# 10_FPGA_misc.net
KiCad netlist of a schematic drawn in Altium Designer
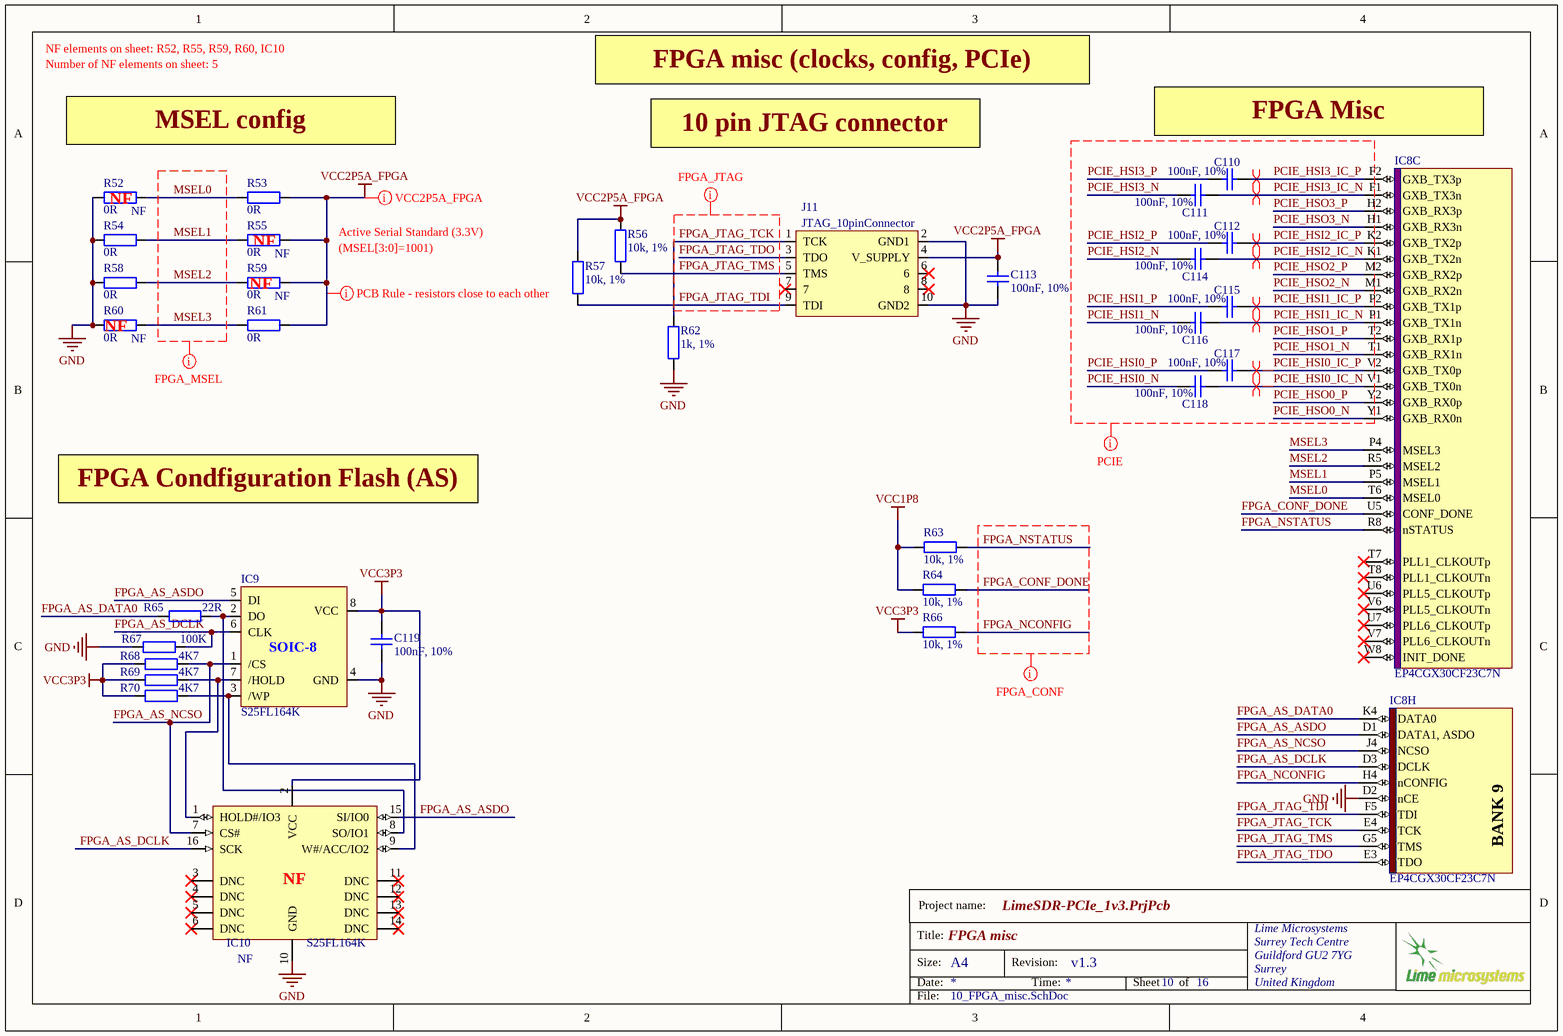
[diagram p0: 10_FPGA_misc.SchDoc]

(export (version "E")
  (design (tool "Eeschema 10.0.6"))
  (components
    (comp (ref "C110")
      (value "100nF, 10%")
      (footprint "CAP0402")
      (fields
        (field (name "TOLERANCE") "10 %")
        (field (name "MANUFACTURER") "Murata Electronics")
        (field (name "MANUFACTURER PART NUMBER") "GRM155R71C104KA88D")
      )
      (libsource (lib "LimeFPGAboard_schLib") (part "Cap_0603"))
    )
    (comp (ref "C111")
      (value "100nF, 10%")
      (footprint "CAP0402")
      (fields
        (field (name "TOLERANCE") "10 %")
        (field (name "MANUFACTURER") "Murata Electronics")
        (field (name "MANUFACTURER PART NUMBER") "GRM155R71C104KA88D")
      )
      (libsource (lib "LimeFPGAboard_schLib") (part "Cap_0603"))
    )
    (comp (ref "C112")
      (value "100nF, 10%")
      (footprint "CAP0402")
      (fields
        (field (name "TOLERANCE") "10 %")
        (field (name "MANUFACTURER") "Murata Electronics")
        (field (name "MANUFACTURER PART NUMBER") "GRM155R71C104KA88D")
      )
      (libsource (lib "LimeFPGAboard_schLib") (part "Cap_0603"))
    )
    (comp (ref "C113")
      (value "100nF, 10%")
      (footprint "CAP0402")
      (fields
        (field (name "TOLERANCE") "10 %")
        (field (name "MANUFACTURER") "Murata Electronics")
        (field (name "MANUFACTURER PART NUMBER") "GRM155R71C104KA88D")
      )
      (libsource (lib "LimeFPGAboard_schLib") (part "Cap_0603"))
    )
    (comp (ref "C114")
      (value "100nF, 10%")
      (footprint "CAP0402")
      (fields
        (field (name "TOLERANCE") "10 %")
        (field (name "MANUFACTURER") "Murata Electronics")
        (field (name "MANUFACTURER PART NUMBER") "GRM155R71C104KA88D")
      )
      (libsource (lib "LimeFPGAboard_schLib") (part "Cap_0603"))
    )
    (comp (ref "C115")
      (value "100nF, 10%")
      (footprint "CAP0402")
      (fields
        (field (name "TOLERANCE") "10 %")
        (field (name "MANUFACTURER") "Murata Electronics")
        (field (name "MANUFACTURER PART NUMBER") "GRM155R71C104KA88D")
      )
      (libsource (lib "LimeFPGAboard_schLib") (part "Cap_0603"))
    )
    (comp (ref "C116")
      (value "100nF, 10%")
      (footprint "CAP0402")
      (fields
        (field (name "TOLERANCE") "10 %")
        (field (name "MANUFACTURER") "Murata Electronics")
        (field (name "MANUFACTURER PART NUMBER") "GRM155R71C104KA88D")
      )
      (libsource (lib "LimeFPGAboard_schLib") (part "Cap_0603"))
    )
    (comp (ref "C117")
      (value "100nF, 10%")
      (footprint "CAP0402")
      (fields
        (field (name "TOLERANCE") "10 %")
        (field (name "MANUFACTURER") "Murata Electronics")
        (field (name "MANUFACTURER PART NUMBER") "GRM155R71C104KA88D")
      )
      (libsource (lib "LimeFPGAboard_schLib") (part "Cap_0603"))
    )
    (comp (ref "C118")
      (value "100nF, 10%")
      (footprint "CAP0402")
      (fields
        (field (name "TOLERANCE") "10 %")
        (field (name "MANUFACTURER") "Murata Electronics")
        (field (name "MANUFACTURER PART NUMBER") "GRM155R71C104KA88D")
      )
      (libsource (lib "LimeFPGAboard_schLib") (part "Cap_0603"))
    )
    (comp (ref "C119")
      (value "100nF, 10%")
      (footprint "CAP0402")
      (fields
        (field (name "TOLERANCE") "10 %")
        (field (name "MANUFACTURER") "Murata Electronics")
        (field (name "MANUFACTURER PART NUMBER") "GRM155R71C104KA88D")
      )
      (libsource (lib "LimeFPGAboard_schLib") (part "Cap_0603"))
    )
    (comp (ref "IC8")
      (value "EP4CGX30CF23C7N")
      (footprint "ALTR-FBGA484_A-200")
      (fields (field (name "MANUFACTURER") "Altera"))
      (libsource (lib "LimeMicroAltiumLib_schLib") (part "EP4CGX30CF23C7N"))
    )
    (comp (ref "IC9")
      (value "S25FL164K")
      (footprint "S25FL164K_WSO8N")
      (fields (field (name "MANUFACTURER") "Cypress Semiconductor Corp"))
      (libsource (lib "LimeMicroAltiumLib_schLib") (part "W25Q32FV"))
    )
    (comp (ref "IC10")
      (value "S25FL164K")
      (footprint "SOIC16_WIDE")
      (fields (field (name "ASSEMBLY INFO") "NF") (field (name "MANUFACTURER") "Cypress Semiconductor Corp"))
      (libsource (lib "LimeMicroAltiumLib_schLib") (part "S25FL032P"))
    )
    (comp (ref "J11")
      (value "JTAG_10pinConnector")
      (footprint "HEADER5x2_SM")
      (fields (field (name "MANUFACTURER") "MOLEX"))
      (libsource (lib "LimeFPGAboard_schLib") (part "JTAG_connector_10pin"))
    )
    (comp (ref "R52")
      (value "0R")
      (footprint "RES0402")
      (fields (field (name "MANUFACTURER") "Yageo") (field (name "ASSEMBLY INFO") "NF"))
      (libsource (lib "LimeFPGAboard_schLib") (part "Res_0402"))
    )
    (comp (ref "R53")
      (value "0R")
      (footprint "RES0402")
      (fields (field (name "MANUFACTURER") "Yageo"))
      (libsource (lib "LimeFPGAboard_schLib") (part "Res_0402"))
    )
    (comp (ref "R54")
      (value "0R")
      (footprint "RES0402")
      (fields (field (name "MANUFACTURER") "Yageo"))
      (libsource (lib "LimeFPGAboard_schLib") (part "Res_0402"))
    )
    (comp (ref "R55")
      (value "0R")
      (footprint "RES0402")
      (fields (field (name "MANUFACTURER") "Yageo") (field (name "ASSEMBLY INFO") "NF"))
      (libsource (lib "LimeFPGAboard_schLib") (part "Res_0402"))
    )
    (comp (ref "R56")
      (value "10k, 1%")
      (footprint "RES0402")
      (fields (field (name "MANUFACTURER") "Yageo") (field (name "TOLERANCE") "±1%"))
      (libsource (lib "LimeMicroAltiumLib_schLib") (part "Res_0402"))
    )
    (comp (ref "R57")
      (value "10k, 1%")
      (footprint "RES0402")
      (fields (field (name "MANUFACTURER") "Yageo") (field (name "TOLERANCE") "±1%"))
      (libsource (lib "LimeMicroAltiumLib_schLib") (part "Res_0402"))
    )
    (comp (ref "R58")
      (value "0R")
      (footprint "RES0402")
      (fields (field (name "MANUFACTURER") "Yageo"))
      (libsource (lib "LimeFPGAboard_schLib") (part "Res_0402"))
    )
    (comp (ref "R59")
      (value "0R")
      (footprint "RES0402")
      (fields (field (name "MANUFACTURER") "Yageo") (field (name "ASSEMBLY INFO") "NF"))
      (libsource (lib "LimeFPGAboard_schLib") (part "Res_0402"))
    )
    (comp (ref "R60")
      (value "0R")
      (footprint "RES0402")
      (fields (field (name "MANUFACTURER") "Yageo") (field (name "ASSEMBLY INFO") "NF"))
      (libsource (lib "LimeFPGAboard_schLib") (part "Res_0402"))
    )
    (comp (ref "R61")
      (value "0R")
      (footprint "RES0402")
      (fields (field (name "MANUFACTURER") "Yageo"))
      (libsource (lib "LimeFPGAboard_schLib") (part "Res_0402"))
    )
    (comp (ref "R62")
      (value "1k, 1%")
      (footprint "RES0402")
      (fields (field (name "MANUFACTURER") "Stackpole Electronics Inc") (field (name "TOLERANCE") "±1%"))
      (libsource (lib "LimeMicroAltiumLib_schLib") (part "Res_0402"))
    )
    (comp (ref "R63")
      (value "10k, 1%")
      (footprint "RES0402")
      (fields (field (name "MANUFACTURER") "Yageo") (field (name "TOLERANCE") "±1%"))
      (libsource (lib "LimeMicroAltiumLib_schLib") (part "Res_0402"))
    )
    (comp (ref "R64")
      (value "10k, 1%")
      (footprint "RES0402")
      (fields (field (name "MANUFACTURER") "Yageo") (field (name "TOLERANCE") "±1%"))
      (libsource (lib "LimeMicroAltiumLib_schLib") (part "Res_0402"))
    )
    (comp (ref "R65")
      (value "22R")
      (footprint "RES0402")
      (fields (field (name "TOLERANCE") "±1%") (field (name "MANUFACTURER") "Yageo"))
      (libsource (lib "LimeFPGAboard_schLib") (part "Res_0402"))
    )
    (comp (ref "R66")
      (value "10k, 1%")
      (footprint "RES0402")
      (fields (field (name "MANUFACTURER") "Yageo") (field (name "TOLERANCE") "±1%"))
      (libsource (lib "LimeMicroAltiumLib_schLib") (part "Res_0402"))
    )
    (comp (ref "R67")
      (value "100K")
      (footprint "RES0402")
      (fields
        (field (name "TOLERANCE") "±5%")
        (field (name "MANUFACTURER") "Panasonic Electronic Components")
      )
      (libsource (lib "LimeFPGAboard_schLib") (part "Res_0402"))
    )
    (comp (ref "R68")
      (value "4K7")
      (footprint "RES0402")
      (fields (field (name "TOLERANCE") "±5%") (field (name "MANUFACTURER") "Stackpole Electronics Inc."))
      (libsource (lib "LimeFPGAboard_schLib") (part "Res_0402"))
    )
    (comp (ref "R69")
      (value "4K7")
      (footprint "RES0402")
      (fields (field (name "TOLERANCE") "±5%") (field (name "MANUFACTURER") "Stackpole Electronics Inc."))
      (libsource (lib "LimeFPGAboard_schLib") (part "Res_0402"))
    )
    (comp (ref "R70")
      (value "4K7")
      (footprint "RES0402")
      (fields (field (name "TOLERANCE") "±5%") (field (name "MANUFACTURER") "Stackpole Electronics Inc."))
      (libsource (lib "LimeFPGAboard_schLib") (part "Res_0402"))
    )
  )
  (nets
    (net (code "1") (name "/FPGA_AS_ASDO") (class "Default")
      (node (ref "IC10") (pin "15") (pinfunction "SI/IO0_15") (pintype "bidirectional"))
      (node (ref "IC8") (pin "D1") (pinfunction "DATA1,_ASDO_D1") (pintype "bidirectional"))
      (node (ref "IC9") (pin "5") (pinfunction "DI_5") (pintype "passive"))
    )
    (net (code "2") (name "/FPGA_AS_DATA0") (class "Default")
      (node (ref "IC8") (pin "K4") (pinfunction "DATA0_K4") (pintype "bidirectional"))
      (node (ref "R65") (pin "2") (pinfunction "2_2") (pintype "passive"))
    )
    (net (code "3") (name "/FPGA_AS_DCLK") (class "Default")
      (node (ref "IC10") (pin "16") (pinfunction "SCK_16") (pintype "input"))
      (node (ref "IC8") (pin "D3") (pinfunction "DCLK_D3") (pintype "bidirectional"))
      (node (ref "IC9") (pin "6") (pinfunction "CLK_6") (pintype "passive"))
      (node (ref "R67") (pin "1") (pinfunction "1_1") (pintype "passive"))
    )
    (net (code "4") (name "/FPGA_AS_NCSO") (class "Default")
      (node (ref "IC10") (pin "7") (pinfunction "CS#_7") (pintype "input"))
      (node (ref "IC8") (pin "J4") (pinfunction "NCSO_J4") (pintype "bidirectional"))
      (node (ref "IC9") (pin "1") (pinfunction "/CS_1") (pintype "passive"))
      (node (ref "R68") (pin "2") (pinfunction "2_2") (pintype "passive"))
    )
    (net (code "5") (name "/FPGA_CONF_DONE") (class "Default")
      (node (ref "IC8") (pin "U5") (pinfunction "CONF_DONE_U5") (pintype "bidirectional"))
      (node (ref "R64") (pin "2") (pinfunction "2_2") (pintype "passive"))
    )
    (net (code "6") (name "/FPGA_JTAG_TCK") (class "Default")
      (node (ref "IC8") (pin "E4") (pinfunction "TCK_E4") (pintype "bidirectional"))
      (node (ref "J11") (pin "1") (pinfunction "TCK_1") (pintype "passive"))
      (node (ref "R62") (pin "1") (pinfunction "1_1") (pintype "passive"))
    )
    (net (code "7") (name "/FPGA_JTAG_TDI") (class "Default")
      (node (ref "IC8") (pin "F5") (pinfunction "TDI_F5") (pintype "bidirectional"))
      (node (ref "J11") (pin "9") (pinfunction "TDI_9") (pintype "passive"))
      (node (ref "R57") (pin "2") (pinfunction "2_2") (pintype "passive"))
    )
    (net (code "8") (name "/FPGA_JTAG_TDO") (class "Default")
      (node (ref "IC8") (pin "E3") (pinfunction "TDO_E3") (pintype "bidirectional"))
      (node (ref "J11") (pin "3") (pinfunction "TDO_3") (pintype "passive"))
    )
    (net (code "9") (name "/FPGA_JTAG_TMS") (class "Default")
      (node (ref "IC8") (pin "G5") (pinfunction "TMS_G5") (pintype "bidirectional"))
      (node (ref "J11") (pin "5") (pinfunction "TMS_5") (pintype "passive"))
      (node (ref "R56") (pin "2") (pinfunction "2_2") (pintype "passive"))
    )
    (net (code "10") (name "/FPGA_NCONFIG") (class "Default")
      (node (ref "IC8") (pin "H4") (pinfunction "nCONFIG_H4") (pintype "bidirectional"))
      (node (ref "R66") (pin "2") (pinfunction "2_2") (pintype "passive"))
    )
    (net (code "11") (name "/FPGA_NSTATUS") (class "Default")
      (node (ref "IC8") (pin "R8") (pinfunction "nSTATUS_R8") (pintype "bidirectional"))
      (node (ref "R63") (pin "2") (pinfunction "2_2") (pintype "passive"))
    )
    (net (code "12") (name "/MSEL0") (class "Default")
      (node (ref "IC8") (pin "T6") (pinfunction "MSEL0_T6") (pintype "bidirectional"))
      (node (ref "R52") (pin "1") (pinfunction "1_1") (pintype "passive"))
      (node (ref "R53") (pin "2") (pinfunction "2_2") (pintype "passive"))
    )
    (net (code "13") (name "/MSEL1") (class "Default")
      (node (ref "IC8") (pin "P5") (pinfunction "MSEL1_P5") (pintype "bidirectional"))
      (node (ref "R54") (pin "1") (pinfunction "1_1") (pintype "passive"))
      (node (ref "R55") (pin "2") (pinfunction "2_2") (pintype "passive"))
    )
    (net (code "14") (name "/MSEL2") (class "Default")
      (node (ref "IC8") (pin "R5") (pinfunction "MSEL2_R5") (pintype "bidirectional"))
      (node (ref "R58") (pin "1") (pinfunction "1_1") (pintype "passive"))
      (node (ref "R59") (pin "2") (pinfunction "2_2") (pintype "passive"))
    )
    (net (code "15") (name "/MSEL3") (class "Default")
      (node (ref "IC8") (pin "P4") (pinfunction "MSEL3_P4") (pintype "bidirectional"))
      (node (ref "R60") (pin "1") (pinfunction "1_1") (pintype "passive"))
      (node (ref "R61") (pin "2") (pinfunction "2_2") (pintype "passive"))
    )
    (net (code "16") (name "/PCIE_HSI0_IC_N") (class "Default")
      (node (ref "C118") (pin "1") (pinfunction "1_1") (pintype "passive"))
      (node (ref "IC8") (pin "V1") (pinfunction "GXB_TX0n_V1") (pintype "bidirectional"))
    )
    (net (code "17") (name "/PCIE_HSI0_IC_P") (class "Default")
      (node (ref "C117") (pin "1") (pinfunction "1_1") (pintype "passive"))
      (node (ref "IC8") (pin "V2") (pinfunction "GXB_TX0p_V2") (pintype "bidirectional"))
    )
    (net (code "18") (name "/PCIE_HSI0_N") (class "Default")
      (node (ref "C118") (pin "2") (pinfunction "2_2") (pintype "passive"))
    )
    (net (code "19") (name "/PCIE_HSI0_P") (class "Default")
      (node (ref "C117") (pin "2") (pinfunction "2_2") (pintype "passive"))
    )
    (net (code "20") (name "/PCIE_HSI1_IC_N") (class "Default")
      (node (ref "C116") (pin "1") (pinfunction "1_1") (pintype "passive"))
      (node (ref "IC8") (pin "P1") (pinfunction "GXB_TX1n_P1") (pintype "bidirectional"))
    )
    (net (code "21") (name "/PCIE_HSI1_IC_P") (class "Default")
      (node (ref "C115") (pin "1") (pinfunction "1_1") (pintype "passive"))
      (node (ref "IC8") (pin "P2") (pinfunction "GXB_TX1p_P2") (pintype "bidirectional"))
    )
    (net (code "22") (name "/PCIE_HSI1_N") (class "Default")
      (node (ref "C116") (pin "2") (pinfunction "2_2") (pintype "passive"))
    )
    (net (code "23") (name "/PCIE_HSI1_P") (class "Default")
      (node (ref "C115") (pin "2") (pinfunction "2_2") (pintype "passive"))
    )
    (net (code "24") (name "/PCIE_HSI2_IC_N") (class "Default")
      (node (ref "C114") (pin "1") (pinfunction "1_1") (pintype "passive"))
      (node (ref "IC8") (pin "K1") (pinfunction "GXB_TX2n_K1") (pintype "bidirectional"))
    )
    (net (code "25") (name "/PCIE_HSI2_IC_P") (class "Default")
      (node (ref "C112") (pin "1") (pinfunction "1_1") (pintype "passive"))
      (node (ref "IC8") (pin "K2") (pinfunction "GXB_TX2p_K2") (pintype "bidirectional"))
    )
    (net (code "26") (name "/PCIE_HSI2_N") (class "Default")
      (node (ref "C114") (pin "2") (pinfunction "2_2") (pintype "passive"))
    )
    (net (code "27") (name "/PCIE_HSI2_P") (class "Default")
      (node (ref "C112") (pin "2") (pinfunction "2_2") (pintype "passive"))
    )
    (net (code "28") (name "/PCIE_HSI3_IC_N") (class "Default")
      (node (ref "C111") (pin "1") (pinfunction "1_1") (pintype "passive"))
      (node (ref "IC8") (pin "F1") (pinfunction "GXB_TX3n_F1") (pintype "bidirectional"))
    )
    (net (code "29") (name "/PCIE_HSI3_IC_P") (class "Default")
      (node (ref "C110") (pin "1") (pinfunction "1_1") (pintype "passive"))
      (node (ref "IC8") (pin "F2") (pinfunction "GXB_TX3p_F2") (pintype "bidirectional"))
    )
    (net (code "30") (name "/PCIE_HSI3_N") (class "Default")
      (node (ref "C111") (pin "2") (pinfunction "2_2") (pintype "passive"))
    )
    (net (code "31") (name "/PCIE_HSI3_P") (class "Default")
      (node (ref "C110") (pin "2") (pinfunction "2_2") (pintype "passive"))
    )
    (net (code "32") (name "/PCIE_HSO0_N") (class "Default")
      (node (ref "IC8") (pin "Y1") (pinfunction "GXB_RX0n_Y1") (pintype "bidirectional"))
    )
    (net (code "33") (name "/PCIE_HSO0_P") (class "Default")
      (node (ref "IC8") (pin "Y2") (pinfunction "GXB_RX0p_Y2") (pintype "bidirectional"))
    )
    (net (code "34") (name "/PCIE_HSO1_N") (class "Default")
      (node (ref "IC8") (pin "T1") (pinfunction "GXB_RX1n_T1") (pintype "bidirectional"))
    )
    (net (code "35") (name "/PCIE_HSO1_P") (class "Default")
      (node (ref "IC8") (pin "T2") (pinfunction "GXB_RX1p_T2") (pintype "bidirectional"))
    )
    (net (code "36") (name "/PCIE_HSO2_N") (class "Default")
      (node (ref "IC8") (pin "M1") (pinfunction "GXB_RX2n_M1") (pintype "bidirectional"))
    )
    (net (code "37") (name "/PCIE_HSO2_P") (class "Default")
      (node (ref "IC8") (pin "M2") (pinfunction "GXB_RX2p_M2") (pintype "bidirectional"))
    )
    (net (code "38") (name "/PCIE_HSO3_N") (class "Default")
      (node (ref "IC8") (pin "H1") (pinfunction "GXB_RX3n_H1") (pintype "bidirectional"))
    )
    (net (code "39") (name "/PCIE_HSO3_P") (class "Default")
      (node (ref "IC8") (pin "H2") (pinfunction "GXB_RX3p_H2") (pintype "bidirectional"))
    )
    (net (code "40") (name "GND") (class "Default")
      (node (ref "C113") (pin "2") (pinfunction "2_2") (pintype "passive"))
      (node (ref "C119") (pin "2") (pinfunction "2_2") (pintype "passive"))
      (node (ref "IC10") (pin "10") (pinfunction "GND_10") (pintype "passive"))
      (node (ref "IC8") (pin "D2") (pinfunction "nCE_D2") (pintype "bidirectional"))
      (node (ref "IC9") (pin "4") (pinfunction "GND_4") (pintype "passive"))
      (node (ref "J11") (pin "10") (pinfunction "GND2_10") (pintype "power_in"))
      (node (ref "J11") (pin "2") (pinfunction "GND1_2") (pintype "power_in"))
      (node (ref "R52") (pin "2") (pinfunction "2_2") (pintype "passive"))
      (node (ref "R54") (pin "2") (pinfunction "2_2") (pintype "passive"))
      (node (ref "R58") (pin "2") (pinfunction "2_2") (pintype "passive"))
      (node (ref "R60") (pin "2") (pinfunction "2_2") (pintype "passive"))
      (node (ref "R62") (pin "2") (pinfunction "2_2") (pintype "passive"))
      (node (ref "R67") (pin "2") (pinfunction "2_2") (pintype "passive"))
    )
    (net (code "41") (name "Net-(IC10-HOLD#{slash}IO3)") (class "Default")
      (node (ref "IC10") (pin "1") (pinfunction "HOLD#/IO3_1") (pintype "bidirectional"))
      (node (ref "IC9") (pin "7") (pinfunction "/HOLD_7") (pintype "passive"))
      (node (ref "R69") (pin "2") (pinfunction "2_2") (pintype "passive"))
    )
    (net (code "42") (name "Net-(IC10-SO{slash}IO1)") (class "Default")
      (node (ref "IC10") (pin "8") (pinfunction "SO/IO1_8") (pintype "bidirectional"))
      (node (ref "IC9") (pin "2") (pinfunction "DO_2") (pintype "passive"))
      (node (ref "R65") (pin "1") (pinfunction "1_1") (pintype "passive"))
    )
    (net (code "43") (name "Net-(IC10-W#{slash}ACC{slash}IO2)") (class "Default")
      (node (ref "IC10") (pin "9") (pinfunction "W#/ACC/IO2_9") (pintype "bidirectional"))
      (node (ref "IC9") (pin "3") (pinfunction "/WP_3") (pintype "passive"))
      (node (ref "R70") (pin "2") (pinfunction "2_2") (pintype "passive"))
    )
    (net (code "44") (name "VCC1P8") (class "Default")
      (node (ref "R63") (pin "1") (pinfunction "1_1") (pintype "passive"))
      (node (ref "R64") (pin "1") (pinfunction "1_1") (pintype "passive"))
    )
    (net (code "45") (name "VCC2P5A_FPGA") (class "Default")
      (node (ref "C113") (pin "1") (pinfunction "1_1") (pintype "passive"))
      (node (ref "J11") (pin "4") (pinfunction "V_SUPPLY_4") (pintype "power_in"))
      (node (ref "R53") (pin "1") (pinfunction "1_1") (pintype "passive"))
      (node (ref "R55") (pin "1") (pinfunction "1_1") (pintype "passive"))
      (node (ref "R56") (pin "1") (pinfunction "1_1") (pintype "passive"))
      (node (ref "R57") (pin "1") (pinfunction "1_1") (pintype "passive"))
      (node (ref "R59") (pin "1") (pinfunction "1_1") (pintype "passive"))
      (node (ref "R61") (pin "1") (pinfunction "1_1") (pintype "passive"))
    )
    (net (code "46") (name "VCC3P3") (class "Default")
      (node (ref "C119") (pin "1") (pinfunction "1_1") (pintype "passive"))
      (node (ref "IC10") (pin "2") (pinfunction "VCC_2") (pintype "power_in"))
      (node (ref "IC9") (pin "8") (pinfunction "VCC_8") (pintype "passive"))
      (node (ref "R66") (pin "1") (pinfunction "1_1") (pintype "passive"))
      (node (ref "R68") (pin "1") (pinfunction "1_1") (pintype "passive"))
      (node (ref "R69") (pin "1") (pinfunction "1_1") (pintype "passive"))
      (node (ref "R70") (pin "1") (pinfunction "1_1") (pintype "passive"))
    )
    (net (code "47") (name "unconnected-(IC8C-INIT_DONE-PadW8)") (class "Default")
      (node (ref "IC8") (pin "W8") (pinfunction "INIT_DONE_W8") (pintype "bidirectional+no_connect"))
    )
    (net (code "48") (name "unconnected-(IC8C-PLL1_CLKOUTn-PadT8)") (class "Default")
      (node (ref "IC8") (pin "T8") (pinfunction "PLL1_CLKOUTn_T8") (pintype "bidirectional+no_connect"))
    )
    (net (code "49") (name "unconnected-(IC8C-PLL1_CLKOUTp-PadT7)") (class "Default")
      (node (ref "IC8") (pin "T7") (pinfunction "PLL1_CLKOUTp_T7") (pintype "bidirectional+no_connect"))
    )
    (net (code "50") (name "unconnected-(IC8C-PLL5_CLKOUTn-PadV6)") (class "Default")
      (node (ref "IC8") (pin "V6") (pinfunction "PLL5_CLKOUTn_V6") (pintype "bidirectional+no_connect"))
    )
    (net (code "51") (name "unconnected-(IC8C-PLL5_CLKOUTp-PadU6)") (class "Default")
      (node (ref "IC8") (pin "U6") (pinfunction "PLL5_CLKOUTp_U6") (pintype "bidirectional+no_connect"))
    )
    (net (code "52") (name "unconnected-(IC8C-PLL6_CLKOUTn-PadV7)") (class "Default")
      (node (ref "IC8") (pin "V7") (pinfunction "PLL6_CLKOUTn_V7") (pintype "bidirectional+no_connect"))
    )
    (net (code "53") (name "unconnected-(IC8C-PLL6_CLKOUTp-PadU7)") (class "Default")
      (node (ref "IC8") (pin "U7") (pinfunction "PLL6_CLKOUTp_U7") (pintype "bidirectional+no_connect"))
    )
    (net (code "54") (name "unconnected-(IC10-DNC-Pad3)") (class "Default")
      (node (ref "IC10") (pin "3") (pinfunction "DNC_3") (pintype "passive+no_connect"))
    )
    (net (code "55") (name "unconnected-(IC10-DNC-Pad4)") (class "Default")
      (node (ref "IC10") (pin "4") (pinfunction "DNC_4") (pintype "passive+no_connect"))
    )
    (net (code "56") (name "unconnected-(IC10-DNC-Pad5)") (class "Default")
      (node (ref "IC10") (pin "5") (pinfunction "DNC_5") (pintype "passive+no_connect"))
    )
    (net (code "57") (name "unconnected-(IC10-DNC-Pad6)") (class "Default")
      (node (ref "IC10") (pin "6") (pinfunction "DNC_6") (pintype "passive+no_connect"))
    )
    (net (code "58") (name "unconnected-(IC10-DNC-Pad11)") (class "Default")
      (node (ref "IC10") (pin "11") (pinfunction "DNC_11") (pintype "passive+no_connect"))
    )
    (net (code "59") (name "unconnected-(IC10-DNC-Pad12)") (class "Default")
      (node (ref "IC10") (pin "12") (pinfunction "DNC_12") (pintype "passive+no_connect"))
    )
    (net (code "60") (name "unconnected-(IC10-DNC-Pad13)") (class "Default")
      (node (ref "IC10") (pin "13") (pinfunction "DNC_13") (pintype "passive+no_connect"))
    )
    (net (code "61") (name "unconnected-(IC10-DNC-Pad14)") (class "Default")
      (node (ref "IC10") (pin "14") (pinfunction "DNC_14") (pintype "passive+no_connect"))
    )
    (net (code "62") (name "unconnected-(J11-Pad6)") (class "Default")
      (node (ref "J11") (pin "6") (pinfunction "6_6") (pintype "passive+no_connect"))
    )
    (net (code "63") (name "unconnected-(J11-Pad7)") (class "Default")
      (node (ref "J11") (pin "7") (pinfunction "7_7") (pintype "passive+no_connect"))
    )
    (net (code "64") (name "unconnected-(J11-Pad8)") (class "Default")
      (node (ref "J11") (pin "8") (pinfunction "8_8") (pintype "passive+no_connect"))
    )
  )
)
